# USBAutoMouse.net
KiCad netlist of a schematic drawn in Altium Designer
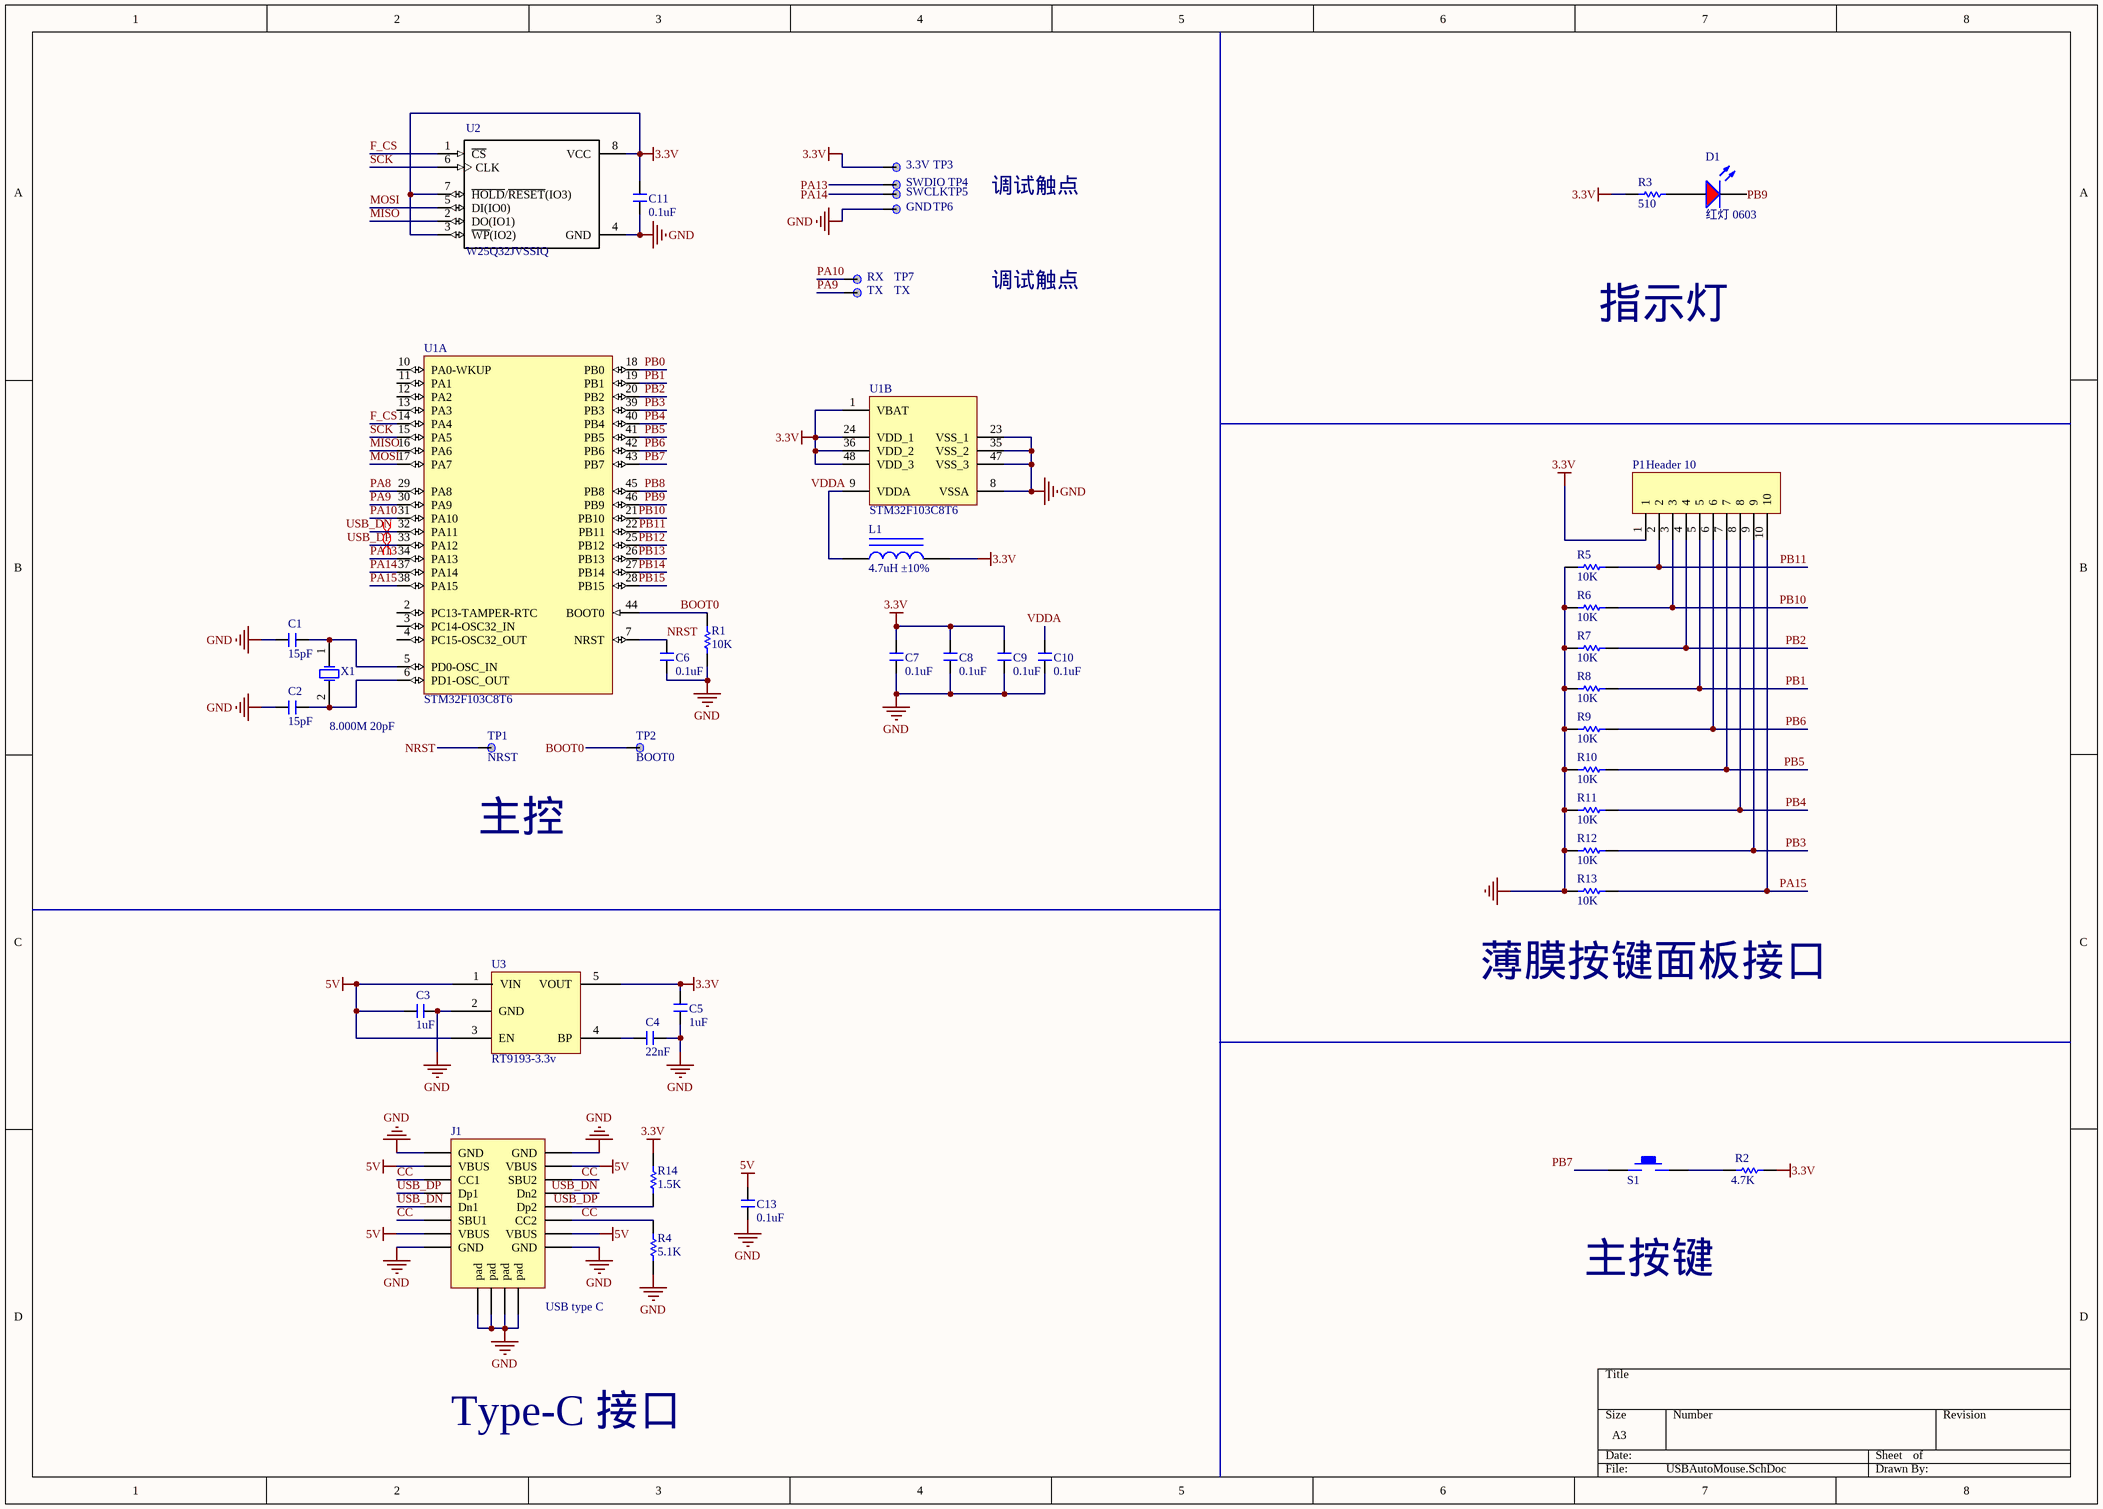
[diagram p0: USBAutoMouse.SchDoc]

(export (version "E")
  (design (tool "Eeschema 10.0.6"))
  (components
    (comp (ref "C1")
      (value "15pF")
      (footprint "C 0603")
      (description "无极性贴片电容")
      (fields (field (name "版权归属") "源创客"))
      (libsource (lib "PMW3901 V1.1") (part "C"))
    )
    (comp (ref "C2")
      (value "15pF")
      (footprint "C 0603")
      (description "无极性贴片电容")
      (fields (field (name "版权归属") "源创客"))
      (libsource (lib "PMW3901 V1.1") (part "C"))
    )
    (comp (ref "C3")
      (value "1uF")
      (footprint "C 0603")
      (description "无极性贴片电容")
      (fields (field (name "版权归属") "源创客"))
      (libsource (lib "PMW3901 V1.1") (part "C"))
    )
    (comp (ref "C4")
      (value "22nF")
      (footprint "C 0603")
      (description "无极性贴片电容")
      (fields (field (name "版权归属") "源创客"))
      (libsource (lib "PMW3901 V1.1") (part "C"))
    )
    (comp (ref "C5")
      (value "1uF")
      (footprint "C 0603")
      (description "无极性贴片电容")
      (fields (field (name "版权归属") "源创客"))
      (libsource (lib "PMW3901 V1.1") (part "C"))
    )
    (comp (ref "C6")
      (value "0.1uF")
      (footprint "C 0603")
      (description "无极性贴片电容")
      (fields (field (name "版权归属") "源创客"))
      (libsource (lib "PMW3901 V1.1") (part "C"))
    )
    (comp (ref "C7")
      (value "0.1uF")
      (footprint "C 0603")
      (description "无极性贴片电容")
      (fields (field (name "版权归属") "源创客"))
      (libsource (lib "PMW3901 V1.1") (part "C"))
    )
    (comp (ref "C8")
      (value "0.1uF")
      (footprint "C 0603")
      (description "无极性贴片电容")
      (fields (field (name "版权归属") "源创客"))
      (libsource (lib "PMW3901 V1.1") (part "C"))
    )
    (comp (ref "C9")
      (value "0.1uF")
      (footprint "C 0603")
      (description "无极性贴片电容")
      (fields (field (name "版权归属") "源创客"))
      (libsource (lib "PMW3901 V1.1") (part "C"))
    )
    (comp (ref "C10")
      (value "0.1uF")
      (footprint "C 0603")
      (description "无极性贴片电容")
      (fields (field (name "版权归属") "源创客"))
      (libsource (lib "PMW3901 V1.1") (part "C"))
    )
    (comp (ref "C11")
      (value "0.1uF")
      (footprint "C 0603")
      (description "无极性贴片电容")
      (fields (field (name "版权归属") "源创客"))
      (libsource (lib "PMW3901 V1.1") (part "C"))
    )
    (comp (ref "C13")
      (value "0.1uF")
      (footprint "C 0603")
      (description "无极性贴片电容")
      (fields (field (name "版权归属") "源创客"))
      (libsource (lib "PMW3901 V1.1") (part "C"))
    )
    (comp (ref "D1")
      (value "红灯 0603")
      (footprint "0603_LED_S1")
      (description "发光二极管")
      (libsource (lib "MiniF401CB") (part "0603 红灯"))
    )
    (comp (ref "J1")
      (value "USB type C")
      (footprint "TYPE-C-USB-17")
      (libsource (lib "LicheeDan") (part "USB_C"))
    )
    (comp (ref "L1")
      (value "4.7uH ±10%")
      (footprint "0603_L")
      (description "贴片电感")
      (libsource (lib "IUD") (part "0603 4.7uH 10%"))
    )
    (comp (ref "P1")
      (value "Header 10")
      (footprint "HDR1X10")
      (description "Header, 10-Pin")
      (fields (field (name "PUBLISHER") "Altium Limited"))
      (libsource (lib "Connectors") (part "Header 10"))
    )
    (comp (ref "R1")
      (value "10K")
      (footprint "0603R")
      (description "Resistor")
      (fields (field (name "PUBLISHER") "Altium Limited"))
      (libsource (lib "MB1137") (part "Res1"))
    )
    (comp (ref "R2")
      (value "4.7K")
      (footprint "0603R")
      (description "Resistor")
      (fields (field (name "PUBLISHER") "Altium Limited"))
      (libsource (lib "MB1137") (part "Res1"))
    )
    (comp (ref "R3")
      (value "510")
      (footprint "0603R")
      (description "Resistor")
      (fields (field (name "PUBLISHER") "Altium Limited"))
      (libsource (lib "MB1137") (part "Res1"))
    )
    (comp (ref "R4")
      (value "5.1K")
      (footprint "0603R")
      (description "Resistor")
      (fields (field (name "PUBLISHER") "Altium Limited"))
      (libsource (lib "MB1137") (part "Res1"))
    )
    (comp (ref "R5")
      (value "10K")
      (footprint "0603R")
      (description "Resistor")
      (fields (field (name "PUBLISHER") "Altium Limited"))
      (libsource (lib "MB1137") (part "Res1"))
    )
    (comp (ref "R6")
      (value "10K")
      (footprint "0603R")
      (description "Resistor")
      (fields (field (name "PUBLISHER") "Altium Limited"))
      (libsource (lib "MB1137") (part "Res1"))
    )
    (comp (ref "R7")
      (value "10K")
      (footprint "0603R")
      (description "Resistor")
      (fields (field (name "PUBLISHER") "Altium Limited"))
      (libsource (lib "MB1137") (part "Res1"))
    )
    (comp (ref "R8")
      (value "10K")
      (footprint "0603R")
      (description "Resistor")
      (fields (field (name "PUBLISHER") "Altium Limited"))
      (libsource (lib "MB1137") (part "Res1"))
    )
    (comp (ref "R9")
      (value "10K")
      (footprint "0603R")
      (description "Resistor")
      (fields (field (name "PUBLISHER") "Altium Limited"))
      (libsource (lib "MB1137") (part "Res1"))
    )
    (comp (ref "R10")
      (value "10K")
      (footprint "0603R")
      (description "Resistor")
      (fields (field (name "PUBLISHER") "Altium Limited"))
      (libsource (lib "MB1137") (part "Res1"))
    )
    (comp (ref "R11")
      (value "10K")
      (footprint "0603R")
      (description "Resistor")
      (fields (field (name "PUBLISHER") "Altium Limited"))
      (libsource (lib "MB1137") (part "Res1"))
    )
    (comp (ref "R12")
      (value "10K")
      (footprint "0603R")
      (description "Resistor")
      (fields (field (name "PUBLISHER") "Altium Limited"))
      (libsource (lib "MB1137") (part "Res1"))
    )
    (comp (ref "R13")
      (value "10K")
      (footprint "0603R")
      (description "Resistor")
      (fields (field (name "PUBLISHER") "Altium Limited"))
      (libsource (lib "MB1137") (part "Res1"))
    )
    (comp (ref "R14")
      (value "1.5K")
      (footprint "0603R")
      (description "Resistor")
      (fields (field (name "PUBLISHER") "Altium Limited"))
      (libsource (lib "MB1137") (part "Res1"))
    )
    (comp (ref "S1")
      (value "KEY")
      (footprint "KEY-12X12X7.5")
      (description "普通轻触按钮")
      (libsource (lib "Devices") (part "KEY"))
    )
    (comp (ref "TP1") (value "NRST") (footprint "TP") (libsource (lib "MB1137") (part "TP")))
    (comp (ref "TP2") (value "BOOT0") (footprint "TP") (libsource (lib "MB1137") (part "TP")))
    (comp (ref "TP3") (value "3.3V") (footprint "TP") (libsource (lib "MB1137") (part "TP")))
    (comp (ref "TP4") (value "SWDIO") (footprint "TP") (libsource (lib "MB1137") (part "TP")))
    (comp (ref "TP5") (value "SWCLK") (footprint "TP") (libsource (lib "MB1137") (part "TP")))
    (comp (ref "TP6") (value "GND") (footprint "TP") (libsource (lib "MB1137") (part "TP")))
    (comp (ref "TP7") (value "RX") (footprint "TP") (libsource (lib "MB1137") (part "TP")))
    (comp (ref "TX") (value "TX") (footprint "TP") (libsource (lib "MB1137") (part "TP")))
    (comp (ref "U1")
      (value "STM32F103C8T6")
      (footprint "STM-LQFP48_L")
      (libsource (lib "STMicroelectronics STM32 F1") (part "STM32F103C8T6"))
    )
    (comp (ref "U2")
      (value "W25Q32JVSSIQ")
      (footprint "*SOIC127P790X216-8N")
      (description "NOR闂瓨涓茶SPI 3V 32Mbit 32M x 1浣?寮曡剼SOIC")
      (fields (field (name "MF") "Winbond"))
      (libsource (lib "W25Q32JVSSIQ") (part "W25Q32JVSSIQ"))
    )
    (comp (ref "U3") (value "RT9193-3.3v") (footprint "SOT-23-5L") (libsource (lib "zhuyix") (part "RT9193")))
    (comp (ref "X1")
      (value "8.000M 20pF")
      (footprint "OSC_2SM_3R2x2R5")
      (description "Crystal Oscillator")
      (fields (field (name "PUBLISHER") "Altium Limited"))
      (libsource (lib "MB1137") (part "XTAL"))
    )
  )
  (nets
    (net (code "2") (name "/BOOT0") (class "Default")
      (node (ref "R1") (pin "2") (pinfunction "2_2") (pintype "passive"))
      (node (ref "TP2") (pin "1") (pinfunction "1_1") (pintype "passive"))
      (node (ref "U1") (pin "44") (pinfunction "BOOT0_44") (pintype "input"))
    )
    (net (code "3") (name "/CC") (class "Default")
      (node (ref "J1") (pin "A5") (pinfunction "CC1_A5") (pintype "passive"))
      (node (ref "J1") (pin "A8") (pinfunction "SBU1_A8") (pintype "passive"))
      (node (ref "J1") (pin "B5") (pinfunction "CC2_B5") (pintype "passive"))
      (node (ref "J1") (pin "B8") (pinfunction "SBU2_B8") (pintype "passive"))
      (node (ref "R4") (pin "1") (pinfunction "1_1") (pintype "passive"))
    )
    (net (code "4") (name "/F_CS") (class "Default")
      (node (ref "U1") (pin "14") (pinfunction "PA4_14") (pintype "bidirectional"))
      (node (ref "U2") (pin "1") (pinfunction "~{CS}_1") (pintype "input"))
    )
    (net (code "5") (name "/MISO") (class "Default")
      (node (ref "U1") (pin "16") (pinfunction "PA6_16") (pintype "bidirectional"))
      (node (ref "U2") (pin "2") (pinfunction "DO(IO1)_2") (pintype "bidirectional"))
    )
    (net (code "6") (name "/MOSI") (class "Default")
      (node (ref "U1") (pin "17") (pinfunction "PA7_17") (pintype "bidirectional"))
      (node (ref "U2") (pin "5") (pinfunction "DI(IO0)_5") (pintype "bidirectional"))
    )
    (net (code "7") (name "/NRST") (class "Default")
      (node (ref "C6") (pin "1") (pinfunction "1_1") (pintype "passive"))
      (node (ref "TP1") (pin "1") (pinfunction "1_1") (pintype "passive"))
      (node (ref "U1") (pin "7") (pinfunction "NRST_7") (pintype "bidirectional"))
    )
    (net (code "8") (name "/PA8") (class "Default")
      (node (ref "U1") (pin "29") (pinfunction "PA8_29") (pintype "bidirectional"))
    )
    (net (code "9") (name "/PA9") (class "Default")
      (node (ref "TX") (pin "1") (pinfunction "1_1") (pintype "passive"))
      (node (ref "U1") (pin "30") (pinfunction "PA9_30") (pintype "bidirectional"))
    )
    (net (code "10") (name "/PA10") (class "Default")
      (node (ref "TP7") (pin "1") (pinfunction "1_1") (pintype "passive"))
      (node (ref "U1") (pin "31") (pinfunction "PA10_31") (pintype "bidirectional"))
    )
    (net (code "11") (name "/PA13") (class "Default")
      (node (ref "TP4") (pin "1") (pinfunction "1_1") (pintype "passive"))
      (node (ref "U1") (pin "34") (pinfunction "PA13_34") (pintype "bidirectional"))
    )
    (net (code "12") (name "/PA14") (class "Default")
      (node (ref "TP5") (pin "1") (pinfunction "1_1") (pintype "passive"))
      (node (ref "U1") (pin "37") (pinfunction "PA14_37") (pintype "bidirectional"))
    )
    (net (code "13") (name "/PA15") (class "Default")
      (node (ref "P1") (pin "10") (pinfunction "10_10") (pintype "passive"))
      (node (ref "R13") (pin "2") (pinfunction "2_2") (pintype "passive"))
      (node (ref "U1") (pin "38") (pinfunction "PA15_38") (pintype "bidirectional"))
    )
    (net (code "14") (name "/PB0") (class "Default")
      (node (ref "U1") (pin "18") (pinfunction "PB0_18") (pintype "bidirectional"))
    )
    (net (code "15") (name "/PB1") (class "Default")
      (node (ref "P1") (pin "5") (pinfunction "5_5") (pintype "passive"))
      (node (ref "R8") (pin "2") (pinfunction "2_2") (pintype "passive"))
      (node (ref "U1") (pin "19") (pinfunction "PB1_19") (pintype "bidirectional"))
    )
    (net (code "16") (name "/PB2") (class "Default")
      (node (ref "P1") (pin "4") (pinfunction "4_4") (pintype "passive"))
      (node (ref "R7") (pin "2") (pinfunction "2_2") (pintype "passive"))
      (node (ref "U1") (pin "20") (pinfunction "PB2_20") (pintype "bidirectional"))
    )
    (net (code "17") (name "/PB3") (class "Default")
      (node (ref "P1") (pin "9") (pinfunction "9_9") (pintype "passive"))
      (node (ref "R12") (pin "2") (pinfunction "2_2") (pintype "passive"))
      (node (ref "U1") (pin "39") (pinfunction "PB3_39") (pintype "bidirectional"))
    )
    (net (code "18") (name "/PB4") (class "Default")
      (node (ref "P1") (pin "8") (pinfunction "8_8") (pintype "passive"))
      (node (ref "R11") (pin "2") (pinfunction "2_2") (pintype "passive"))
      (node (ref "U1") (pin "40") (pinfunction "PB4_40") (pintype "bidirectional"))
    )
    (net (code "19") (name "/PB5") (class "Default")
      (node (ref "P1") (pin "7") (pinfunction "7_7") (pintype "passive"))
      (node (ref "R10") (pin "2") (pinfunction "2_2") (pintype "passive"))
      (node (ref "U1") (pin "41") (pinfunction "PB5_41") (pintype "bidirectional"))
    )
    (net (code "20") (name "/PB6") (class "Default")
      (node (ref "P1") (pin "6") (pinfunction "6_6") (pintype "passive"))
      (node (ref "R9") (pin "2") (pinfunction "2_2") (pintype "passive"))
      (node (ref "U1") (pin "42") (pinfunction "PB6_42") (pintype "bidirectional"))
    )
    (net (code "21") (name "/PB7") (class "Default")
      (node (ref "S1") (pin "1") (pinfunction "1_1") (pintype "passive"))
      (node (ref "U1") (pin "43") (pinfunction "PB7_43") (pintype "bidirectional"))
    )
    (net (code "22") (name "/PB8") (class "Default")
      (node (ref "U1") (pin "45") (pinfunction "PB8_45") (pintype "bidirectional"))
    )
    (net (code "23") (name "/PB9") (class "Default")
      (node (ref "D1") (pin "K") (pinfunction "K_K") (pintype "passive"))
      (node (ref "U1") (pin "46") (pinfunction "PB9_46") (pintype "bidirectional"))
    )
    (net (code "24") (name "/PB10") (class "Default")
      (node (ref "P1") (pin "3") (pinfunction "3_3") (pintype "passive"))
      (node (ref "R6") (pin "2") (pinfunction "2_2") (pintype "passive"))
      (node (ref "U1") (pin "21") (pinfunction "PB10_21") (pintype "bidirectional"))
    )
    (net (code "25") (name "/PB11") (class "Default")
      (node (ref "P1") (pin "2") (pinfunction "2_2") (pintype "passive"))
      (node (ref "R5") (pin "2") (pinfunction "2_2") (pintype "passive"))
      (node (ref "U1") (pin "22") (pinfunction "PB11_22") (pintype "bidirectional"))
    )
    (net (code "26") (name "/PB12") (class "Default")
      (node (ref "U1") (pin "25") (pinfunction "PB12_25") (pintype "bidirectional"))
    )
    (net (code "27") (name "/PB13") (class "Default")
      (node (ref "U1") (pin "26") (pinfunction "PB13_26") (pintype "bidirectional"))
    )
    (net (code "28") (name "/PB14") (class "Default")
      (node (ref "U1") (pin "27") (pinfunction "PB14_27") (pintype "bidirectional"))
    )
    (net (code "29") (name "/PB15") (class "Default")
      (node (ref "U1") (pin "28") (pinfunction "PB15_28") (pintype "bidirectional"))
    )
    (net (code "30") (name "/SCK") (class "Default")
      (node (ref "U1") (pin "15") (pinfunction "PA5_15") (pintype "bidirectional"))
      (node (ref "U2") (pin "6") (pinfunction "CLK_6") (pintype "input"))
    )
    (net (code "31") (name "/USB_DN") (class "Default")
      (node (ref "J1") (pin "A7") (pinfunction "Dn1_A7") (pintype "passive"))
      (node (ref "J1") (pin "B7") (pinfunction "Dn2_B7") (pintype "passive"))
      (node (ref "U1") (pin "32") (pinfunction "PA11_32") (pintype "bidirectional"))
    )
    (net (code "32") (name "/USB_DP") (class "Default")
      (node (ref "J1") (pin "A6") (pinfunction "Dp1_A6") (pintype "passive"))
      (node (ref "J1") (pin "B6") (pinfunction "Dp2_B6") (pintype "passive"))
      (node (ref "R14") (pin "2") (pinfunction "2_2") (pintype "passive"))
      (node (ref "U1") (pin "33") (pinfunction "PA12_33") (pintype "bidirectional"))
    )
    (net (code "33") (name "/VDDA") (class "Default")
      (node (ref "C10") (pin "1") (pinfunction "1_1") (pintype "passive"))
      (node (ref "L1") (pin "1") (pinfunction "1_1") (pintype "passive"))
      (node (ref "U1") (pin "9") (pinfunction "VDDA_9") (pintype "power_in"))
    )
    (net (code "34") (name "3.3V") (class "Default")
      (node (ref "C11") (pin "1") (pinfunction "1_1") (pintype "passive"))
      (node (ref "C5") (pin "2") (pinfunction "2_2") (pintype "passive"))
      (node (ref "C7") (pin "1") (pinfunction "1_1") (pintype "passive"))
      (node (ref "C8") (pin "1") (pinfunction "1_1") (pintype "passive"))
      (node (ref "C9") (pin "1") (pinfunction "1_1") (pintype "passive"))
      (node (ref "L1") (pin "2") (pinfunction "2_2") (pintype "passive"))
      (node (ref "P1") (pin "1") (pinfunction "1_1") (pintype "passive"))
      (node (ref "R14") (pin "1") (pinfunction "1_1") (pintype "passive"))
      (node (ref "R2") (pin "1") (pinfunction "1_1") (pintype "passive"))
      (node (ref "R3") (pin "2") (pinfunction "2_2") (pintype "passive"))
      (node (ref "TP3") (pin "1") (pinfunction "1_1") (pintype "passive"))
      (node (ref "U1") (pin "1") (pinfunction "VBAT_1") (pintype "power_in"))
      (node (ref "U1") (pin "24") (pinfunction "VDD_1_24") (pintype "power_in"))
      (node (ref "U1") (pin "36") (pinfunction "VDD_2_36") (pintype "power_in"))
      (node (ref "U1") (pin "48") (pinfunction "VDD_3_48") (pintype "power_in"))
      (node (ref "U2") (pin "3") (pinfunction "~{WP}(IO2)_3") (pintype "bidirectional"))
      (node (ref "U2") (pin "7") (pinfunction "~{HOLD}/~{RESET}(IO3)_7") (pintype "bidirectional"))
      (node (ref "U2") (pin "8") (pinfunction "VCC_8") (pintype "power_in"))
      (node (ref "U3") (pin "5") (pinfunction "VOUT_5") (pintype "passive"))
    )
    (net (code "35") (name "5V") (class "Default")
      (node (ref "C13") (pin "2") (pinfunction "2_2") (pintype "passive"))
      (node (ref "C3") (pin "1") (pinfunction "1_1") (pintype "passive"))
      (node (ref "J1") (pin "A4") (pinfunction "VBUS_A4") (pintype "passive"))
      (node (ref "J1") (pin "A9") (pinfunction "VBUS_A9") (pintype "passive"))
      (node (ref "J1") (pin "B4") (pinfunction "VBUS_B4") (pintype "passive"))
      (node (ref "J1") (pin "B9") (pinfunction "VBUS_B9") (pintype "passive"))
      (node (ref "U3") (pin "1") (pinfunction "VIN_1") (pintype "passive"))
      (node (ref "U3") (pin "3") (pinfunction "EN_3") (pintype "passive"))
    )
    (net (code "36") (name "GND") (class "Default")
      (node (ref "C1") (pin "1") (pinfunction "1_1") (pintype "passive"))
      (node (ref "C10") (pin "2") (pinfunction "2_2") (pintype "passive"))
      (node (ref "C11") (pin "2") (pinfunction "2_2") (pintype "passive"))
      (node (ref "C13") (pin "1") (pinfunction "1_1") (pintype "passive"))
      (node (ref "C2") (pin "1") (pinfunction "1_1") (pintype "passive"))
      (node (ref "C3") (pin "2") (pinfunction "2_2") (pintype "passive"))
      (node (ref "C4") (pin "2") (pinfunction "2_2") (pintype "passive"))
      (node (ref "C5") (pin "1") (pinfunction "1_1") (pintype "passive"))
      (node (ref "C6") (pin "2") (pinfunction "2_2") (pintype "passive"))
      (node (ref "C7") (pin "2") (pinfunction "2_2") (pintype "passive"))
      (node (ref "C8") (pin "2") (pinfunction "2_2") (pintype "passive"))
      (node (ref "C9") (pin "2") (pinfunction "2_2") (pintype "passive"))
      (node (ref "J1") (pin "0") (pinfunction "pad_0") (pintype "passive"))
      (node (ref "J1") (pin "A1") (pinfunction "GND_A1") (pintype "passive"))
      (node (ref "J1") (pin "A12") (pinfunction "GND_A12") (pintype "passive"))
      (node (ref "J1") (pin "B1") (pinfunction "GND_B1") (pintype "passive"))
      (node (ref "J1") (pin "B12") (pinfunction "GND_B12") (pintype "passive"))
      (node (ref "R1") (pin "1") (pinfunction "1_1") (pintype "passive"))
      (node (ref "R10") (pin "1") (pinfunction "1_1") (pintype "passive"))
      (node (ref "R11") (pin "1") (pinfunction "1_1") (pintype "passive"))
      (node (ref "R12") (pin "1") (pinfunction "1_1") (pintype "passive"))
      (node (ref "R13") (pin "1") (pinfunction "1_1") (pintype "passive"))
      (node (ref "R4") (pin "2") (pinfunction "2_2") (pintype "passive"))
      (node (ref "R5") (pin "1") (pinfunction "1_1") (pintype "passive"))
      (node (ref "R6") (pin "1") (pinfunction "1_1") (pintype "passive"))
      (node (ref "R7") (pin "1") (pinfunction "1_1") (pintype "passive"))
      (node (ref "R8") (pin "1") (pinfunction "1_1") (pintype "passive"))
      (node (ref "R9") (pin "1") (pinfunction "1_1") (pintype "passive"))
      (node (ref "TP6") (pin "1") (pinfunction "1_1") (pintype "passive"))
      (node (ref "U1") (pin "23") (pinfunction "VSS_1_23") (pintype "power_in"))
      (node (ref "U1") (pin "35") (pinfunction "VSS_2_35") (pintype "power_in"))
      (node (ref "U1") (pin "47") (pinfunction "VSS_3_47") (pintype "power_in"))
      (node (ref "U1") (pin "8") (pinfunction "VSSA_8") (pintype "power_in"))
      (node (ref "U2") (pin "4") (pinfunction "GND_4") (pintype "power_in"))
      (node (ref "U3") (pin "2") (pinfunction "GND_2") (pintype "passive"))
    )
    (net (code "37") (name "Net-(D1-PadA)") (class "Default")
      (node (ref "D1") (pin "A") (pinfunction "A_A") (pintype "passive"))
      (node (ref "R3") (pin "1") (pinfunction "1_1") (pintype "passive"))
    )
    (net (code "38") (name "Net-(R2-Pad2)") (class "Default")
      (node (ref "R2") (pin "2") (pinfunction "2_2") (pintype "passive"))
      (node (ref "S1") (pin "2") (pinfunction "2_2") (pintype "passive"))
    )
    (net (code "39") (name "Net-(U1A-PD0-OSC_IN)") (class "Default")
      (node (ref "C1") (pin "2") (pinfunction "2_2") (pintype "passive"))
      (node (ref "U1") (pin "5") (pinfunction "PD0-OSC_IN_5") (pintype "bidirectional"))
      (node (ref "X1") (pin "1") (pinfunction "OSC1_1") (pintype "passive"))
    )
    (net (code "40") (name "Net-(U1A-PD1-OSC_OUT)") (class "Default")
      (node (ref "C2") (pin "2") (pinfunction "2_2") (pintype "passive"))
      (node (ref "U1") (pin "6") (pinfunction "PD1-OSC_OUT_6") (pintype "bidirectional"))
      (node (ref "X1") (pin "2") (pinfunction "OSC2_2") (pintype "passive"))
    )
    (net (code "41") (name "Net-(U3-BP)") (class "Default")
      (node (ref "C4") (pin "1") (pinfunction "1_1") (pintype "passive"))
      (node (ref "U3") (pin "4") (pinfunction "BP_4") (pintype "passive"))
    )
    (net (code "42") (name "unconnected-(U1A-PA0-WKUP-Pad10)") (class "Default")
      (node (ref "U1") (pin "10") (pinfunction "PA0-WKUP_10") (pintype "bidirectional"))
    )
    (net (code "43") (name "unconnected-(U1A-PA1-Pad11)") (class "Default")
      (node (ref "U1") (pin "11") (pinfunction "PA1_11") (pintype "bidirectional"))
    )
    (net (code "44") (name "unconnected-(U1A-PA2-Pad12)") (class "Default")
      (node (ref "U1") (pin "12") (pinfunction "PA2_12") (pintype "bidirectional"))
    )
    (net (code "45") (name "unconnected-(U1A-PA3-Pad13)") (class "Default")
      (node (ref "U1") (pin "13") (pinfunction "PA3_13") (pintype "bidirectional"))
    )
    (net (code "46") (name "unconnected-(U1A-PC13-TAMPER-RTC-Pad2)") (class "Default")
      (node (ref "U1") (pin "2") (pinfunction "PC13-TAMPER-RTC_2") (pintype "bidirectional"))
    )
    (net (code "47") (name "unconnected-(U1A-PC14-OSC32_IN-Pad3)") (class "Default")
      (node (ref "U1") (pin "3") (pinfunction "PC14-OSC32_IN_3") (pintype "bidirectional"))
    )
    (net (code "48") (name "unconnected-(U1A-PC15-OSC32_OUT-Pad4)") (class "Default")
      (node (ref "U1") (pin "4") (pinfunction "PC15-OSC32_OUT_4") (pintype "bidirectional"))
    )
  )
)
